# theremin.net
KiCad netlist of a schematic drawn in Altium Designer
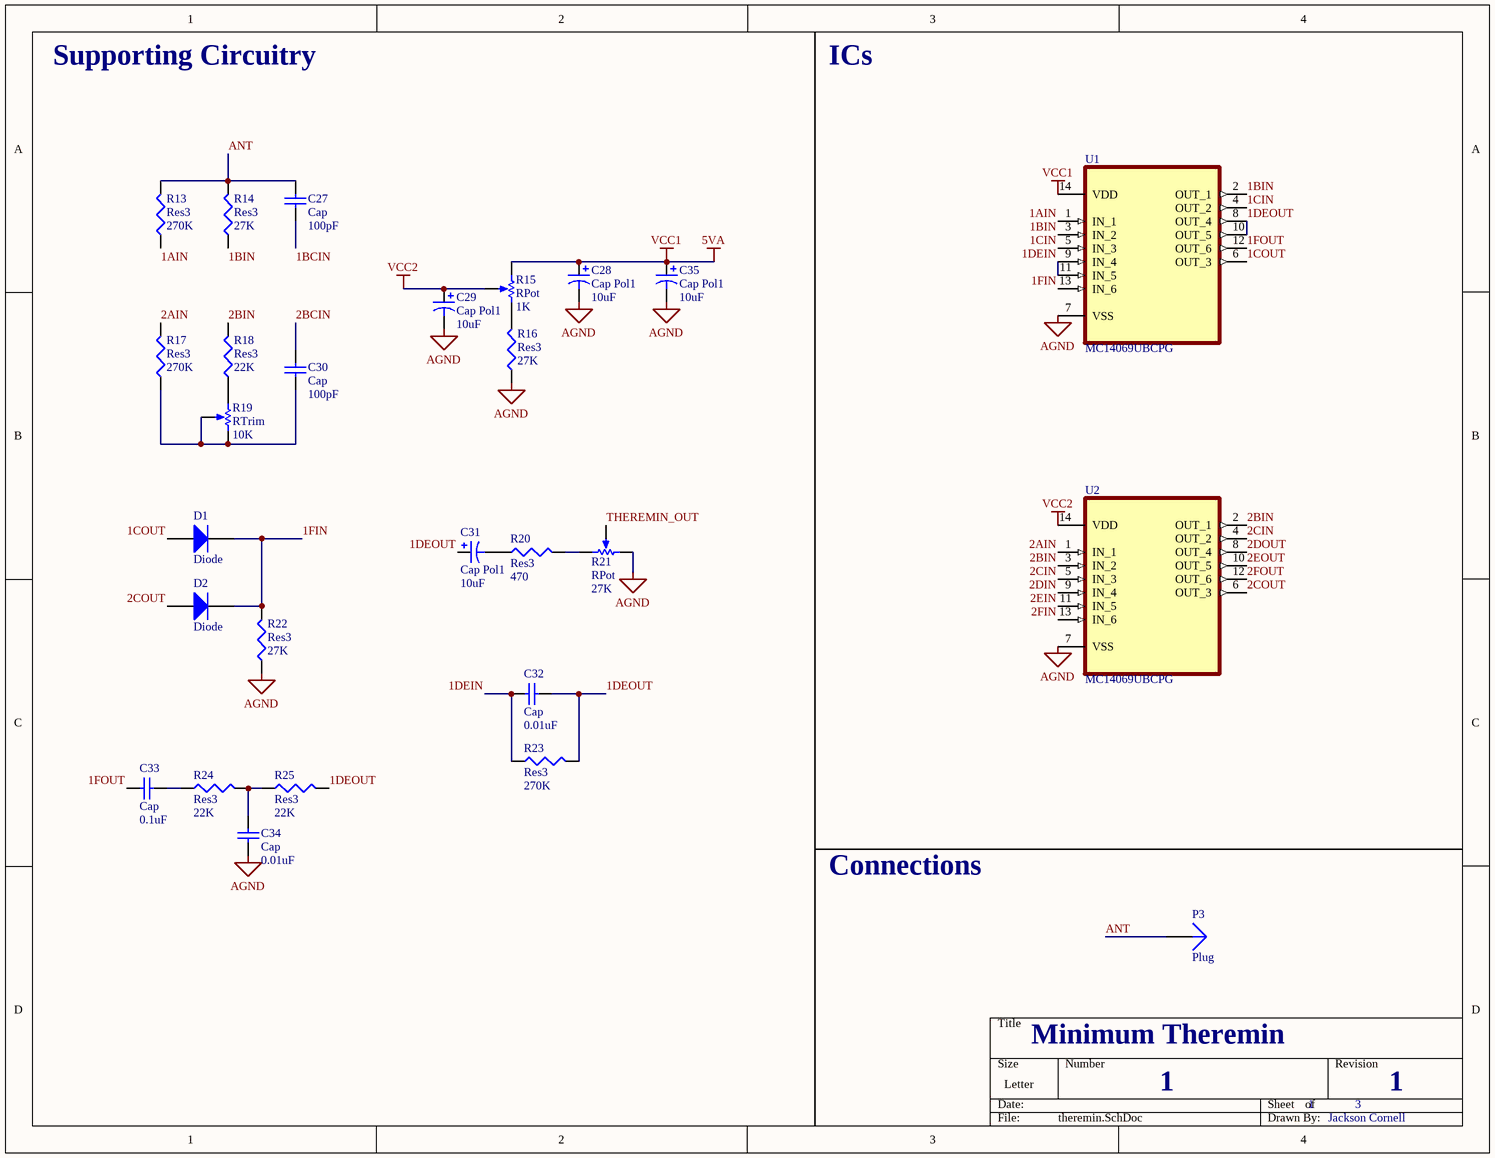
[diagram p0: theremin.SchDoc]

(export (version "E")
  (design (tool "Eeschema 10.0.6"))
  (components
    (comp (ref "C27")
      (value "Cap")
      (footprint "RAD-0.3")
      (description "Capacitor")
      (fields (field (name "ALTIUM_VALUE") "100pF") (field (name "PUBLISHER") "Altium Limited"))
      (libsource (lib "Miscellaneous Devices") (part "Cap"))
    )
    (comp (ref "C28")
      (value "Cap Pol1")
      (footprint "RB7.6-15")
      (description "Polarized Capacitor (Radial)")
      (fields (field (name "ALTIUM_VALUE") "10uF") (field (name "PUBLISHER") "Altium Limited"))
      (libsource (lib "Miscellaneous Devices") (part "Cap Pol1"))
    )
    (comp (ref "C29")
      (value "Cap Pol1")
      (footprint "RB7.6-15")
      (description "Polarized Capacitor (Radial)")
      (fields (field (name "ALTIUM_VALUE") "10uF") (field (name "PUBLISHER") "Altium Limited"))
      (libsource (lib "Miscellaneous Devices") (part "Cap Pol1"))
    )
    (comp (ref "C30")
      (value "Cap")
      (footprint "RAD-0.3")
      (description "Capacitor")
      (fields (field (name "ALTIUM_VALUE") "100pF") (field (name "PUBLISHER") "Altium Limited"))
      (libsource (lib "Miscellaneous Devices") (part "Cap"))
    )
    (comp (ref "C31")
      (value "Cap Pol1")
      (footprint "RB7.6-15")
      (description "Polarized Capacitor (Radial)")
      (fields (field (name "ALTIUM_VALUE") "10uF") (field (name "PUBLISHER") "Altium Limited"))
      (libsource (lib "Miscellaneous Devices") (part "Cap Pol1"))
    )
    (comp (ref "C32")
      (value "Cap")
      (footprint "RAD-0.3")
      (description "Capacitor")
      (fields (field (name "ALTIUM_VALUE") "0.01uF") (field (name "PUBLISHER") "Altium Limited"))
      (libsource (lib "Miscellaneous Devices") (part "Cap"))
    )
    (comp (ref "C33")
      (value "Cap")
      (footprint "RAD-0.3")
      (description "Capacitor")
      (fields (field (name "ALTIUM_VALUE") "0.1uF") (field (name "PUBLISHER") "Altium Limited"))
      (libsource (lib "Miscellaneous Devices") (part "Cap"))
    )
    (comp (ref "C34")
      (value "Cap")
      (footprint "RAD-0.3")
      (description "Capacitor")
      (fields (field (name "ALTIUM_VALUE") "0.01uF") (field (name "PUBLISHER") "Altium Limited"))
      (libsource (lib "Miscellaneous Devices") (part "Cap"))
    )
    (comp (ref "C35")
      (value "Cap Pol1")
      (footprint "RB7.6-15")
      (description "Polarized Capacitor (Radial)")
      (fields (field (name "ALTIUM_VALUE") "10uF") (field (name "PUBLISHER") "Altium Limited"))
      (libsource (lib "Miscellaneous Devices") (part "Cap Pol1"))
    )
    (comp (ref "D1")
      (value "Diode")
      (footprint "SMC")
      (description "Default Diode")
      (fields (field (name "PUBLISHER") "Altium Limited"))
      (libsource (lib "Miscellaneous Devices") (part "Diode"))
    )
    (comp (ref "D2")
      (value "Diode")
      (footprint "SMC")
      (description "Default Diode")
      (fields (field (name "PUBLISHER") "Altium Limited"))
      (libsource (lib "Miscellaneous Devices") (part "Diode"))
    )
    (comp (ref "P3")
      (value "Plug")
      (footprint "PIN1")
      (fields (field (name "PUBLISHER") "Altium Limited"))
      (libsource (lib "Miscellaneous Connectors") (part "Plug"))
    )
    (comp (ref "R13")
      (value "Res3")
      (footprint "J1-0603")
      (description "Resistor")
      (fields (field (name "ALTIUM_VALUE") "270K") (field (name "PUBLISHER") "Altium Limited"))
      (libsource (lib "Miscellaneous Devices") (part "Res3"))
    )
    (comp (ref "R14")
      (value "Res3")
      (footprint "J1-0603")
      (description "Resistor")
      (fields (field (name "ALTIUM_VALUE") "27K") (field (name "PUBLISHER") "Altium Limited"))
      (libsource (lib "Miscellaneous Devices") (part "Res3"))
    )
    (comp (ref "R15")
      (value "RPot")
      (footprint "VR5")
      (description "Potentiometer")
      (fields (field (name "ALTIUM_VALUE") "1K") (field (name "PUBLISHER") "Altium Limited"))
      (libsource (lib "Miscellaneous Devices") (part "RPot"))
    )
    (comp (ref "R16")
      (value "Res3")
      (footprint "J1-0603")
      (description "Resistor")
      (fields (field (name "ALTIUM_VALUE") "27K") (field (name "PUBLISHER") "Altium Limited"))
      (libsource (lib "Miscellaneous Devices") (part "Res3"))
    )
    (comp (ref "R17")
      (value "Res3")
      (footprint "J1-0603")
      (description "Resistor")
      (fields (field (name "ALTIUM_VALUE") "270K") (field (name "PUBLISHER") "Altium Limited"))
      (libsource (lib "Miscellaneous Devices") (part "Res3"))
    )
    (comp (ref "R18")
      (value "Res3")
      (footprint "J1-0603")
      (description "Resistor")
      (fields (field (name "ALTIUM_VALUE") "22K") (field (name "PUBLISHER") "Altium Limited"))
      (libsource (lib "Miscellaneous Devices") (part "Res3"))
    )
    (comp (ref "R19")
      (value "RTrim")
      (footprint "VR5")
      (description "Potentiometer")
      (fields (field (name "ALTIUM_VALUE") "10K") (field (name "PUBLISHER") "Altium Limited"))
      (libsource (lib "Miscellaneous Devices") (part "RPot"))
    )
    (comp (ref "R20")
      (value "Res3")
      (footprint "J1-0603")
      (description "Resistor")
      (fields (field (name "ALTIUM_VALUE") "470") (field (name "PUBLISHER") "Altium Limited"))
      (libsource (lib "Miscellaneous Devices") (part "Res3"))
    )
    (comp (ref "R21")
      (value "RPot")
      (footprint "VR5")
      (description "Potentiometer")
      (fields (field (name "ALTIUM_VALUE") "27K") (field (name "PUBLISHER") "Altium Limited"))
      (libsource (lib "Miscellaneous Devices") (part "RPot"))
    )
    (comp (ref "R22")
      (value "Res3")
      (footprint "J1-0603")
      (description "Resistor")
      (fields (field (name "ALTIUM_VALUE") "27K") (field (name "PUBLISHER") "Altium Limited"))
      (libsource (lib "Miscellaneous Devices") (part "Res3"))
    )
    (comp (ref "R23")
      (value "Res3")
      (footprint "J1-0603")
      (description "Resistor")
      (fields (field (name "ALTIUM_VALUE") "270K") (field (name "PUBLISHER") "Altium Limited"))
      (libsource (lib "Miscellaneous Devices") (part "Res3"))
    )
    (comp (ref "R24")
      (value "Res3")
      (footprint "J1-0603")
      (description "Resistor")
      (fields (field (name "ALTIUM_VALUE") "22K") (field (name "PUBLISHER") "Altium Limited"))
      (libsource (lib "Miscellaneous Devices") (part "Res3"))
    )
    (comp (ref "R25")
      (value "Res3")
      (footprint "J1-0603")
      (description "Resistor")
      (fields (field (name "ALTIUM_VALUE") "22K") (field (name "PUBLISHER") "Altium Limited"))
      (libsource (lib "Miscellaneous Devices") (part "Res3"))
    )
    (comp (ref "U1")
      (value "MC14069UBCPG")
      (footprint "DIP254P762X469-14")
      (description "Inverter IC 6 Channel - 14-PDIP")
      (fields (field (name "MF") "ON Semiconductor"))
      (libsource (lib "MC14069UBCPG") (part "MC14069UBCPG"))
    )
    (comp (ref "U2")
      (value "MC14069UBCPG")
      (footprint "DIP254P762X469-14")
      (description "Inverter IC 6 Channel - 14-PDIP")
      (fields (field (name "MF") "ON Semiconductor"))
      (libsource (lib "MC14069UBCPG") (part "MC14069UBCPG"))
    )
  )
  (nets
    (net (code "1") (name "/1AIN") (class "Default")
      (node (ref "R13") (pin "1") (pinfunction "1_1") (pintype "passive"))
      (node (ref "U1") (pin "1") (pinfunction "IN_1_1") (pintype "input"))
    )
    (net (code "2") (name "/1BCIN") (class "Default")
      (node (ref "C27") (pin "1") (pinfunction "1_1") (pintype "passive"))
    )
    (net (code "3") (name "/1BIN") (class "Default")
      (node (ref "R14") (pin "1") (pinfunction "1_1") (pintype "passive"))
      (node (ref "U1") (pin "2") (pinfunction "OUT_1_2") (pintype "output"))
      (node (ref "U1") (pin "3") (pinfunction "IN_2_3") (pintype "input"))
    )
    (net (code "4") (name "/1CIN") (class "Default")
      (node (ref "U1") (pin "4") (pinfunction "OUT_2_4") (pintype "output"))
      (node (ref "U1") (pin "5") (pinfunction "IN_3_5") (pintype "input"))
    )
    (net (code "5") (name "/1COUT") (class "Default")
      (node (ref "D1") (pin "1") (pinfunction "A_1") (pintype "passive"))
      (node (ref "U1") (pin "6") (pinfunction "OUT_3_6") (pintype "output"))
    )
    (net (code "6") (name "/1DEIN") (class "Default")
      (node (ref "C32") (pin "1") (pinfunction "1_1") (pintype "passive"))
      (node (ref "R23") (pin "1") (pinfunction "1_1") (pintype "passive"))
      (node (ref "U1") (pin "11") (pinfunction "IN_5_11") (pintype "input"))
      (node (ref "U1") (pin "9") (pinfunction "IN_4_9") (pintype "input"))
    )
    (net (code "7") (name "/1DEOUT") (class "Default")
      (node (ref "C31") (pin "1") (pinfunction "1_1") (pintype "passive"))
      (node (ref "C32") (pin "2") (pinfunction "2_2") (pintype "passive"))
      (node (ref "R23") (pin "2") (pinfunction "2_2") (pintype "passive"))
      (node (ref "R25") (pin "2") (pinfunction "2_2") (pintype "passive"))
      (node (ref "U1") (pin "10") (pinfunction "OUT_5_10") (pintype "output"))
      (node (ref "U1") (pin "8") (pinfunction "OUT_4_8") (pintype "output"))
    )
    (net (code "8") (name "/1FIN") (class "Default")
      (node (ref "D1") (pin "2") (pinfunction "K_2") (pintype "passive"))
      (node (ref "D2") (pin "2") (pinfunction "K_2") (pintype "passive"))
      (node (ref "R22") (pin "2") (pinfunction "2_2") (pintype "passive"))
      (node (ref "U1") (pin "13") (pinfunction "IN_6_13") (pintype "input"))
    )
    (net (code "9") (name "/1FOUT") (class "Default")
      (node (ref "C33") (pin "1") (pinfunction "1_1") (pintype "passive"))
      (node (ref "U1") (pin "12") (pinfunction "OUT_6_12") (pintype "output"))
    )
    (net (code "10") (name "/2AIN") (class "Default")
      (node (ref "R17") (pin "2") (pinfunction "2_2") (pintype "passive"))
      (node (ref "U2") (pin "1") (pinfunction "IN_1_1") (pintype "input"))
    )
    (net (code "11") (name "/2BCIN") (class "Default")
      (node (ref "C30") (pin "2") (pinfunction "2_2") (pintype "passive"))
    )
    (net (code "12") (name "/2BIN") (class "Default")
      (node (ref "R18") (pin "2") (pinfunction "2_2") (pintype "passive"))
      (node (ref "U2") (pin "2") (pinfunction "OUT_1_2") (pintype "output"))
      (node (ref "U2") (pin "3") (pinfunction "IN_2_3") (pintype "input"))
    )
    (net (code "13") (name "/2CIN") (class "Default")
      (node (ref "U2") (pin "4") (pinfunction "OUT_2_4") (pintype "output"))
      (node (ref "U2") (pin "5") (pinfunction "IN_3_5") (pintype "input"))
    )
    (net (code "14") (name "/2COUT") (class "Default")
      (node (ref "D2") (pin "1") (pinfunction "A_1") (pintype "passive"))
      (node (ref "U2") (pin "6") (pinfunction "OUT_3_6") (pintype "output"))
    )
    (net (code "15") (name "/2DIN") (class "Default")
      (node (ref "U2") (pin "9") (pinfunction "IN_4_9") (pintype "input"))
    )
    (net (code "16") (name "/2DOUT") (class "Default")
      (node (ref "U2") (pin "8") (pinfunction "OUT_4_8") (pintype "output"))
    )
    (net (code "17") (name "/2EIN") (class "Default")
      (node (ref "U2") (pin "11") (pinfunction "IN_5_11") (pintype "input"))
    )
    (net (code "18") (name "/2EOUT") (class "Default")
      (node (ref "U2") (pin "10") (pinfunction "OUT_5_10") (pintype "output"))
    )
    (net (code "19") (name "/2FIN") (class "Default")
      (node (ref "U2") (pin "13") (pinfunction "IN_6_13") (pintype "input"))
    )
    (net (code "20") (name "/2FOUT") (class "Default")
      (node (ref "U2") (pin "12") (pinfunction "OUT_6_12") (pintype "output"))
    )
    (net (code "21") (name "/ANT") (class "Default")
      (node (ref "C27") (pin "2") (pinfunction "2_2") (pintype "passive"))
      (node (ref "P3") (pin "1") (pinfunction "1_1") (pintype "passive"))
      (node (ref "R13") (pin "2") (pinfunction "2_2") (pintype "passive"))
      (node (ref "R14") (pin "2") (pinfunction "2_2") (pintype "passive"))
    )
    (net (code "22") (name "/THEREMIN_OUT") (class "Default")
      (node (ref "R21") (pin "3") (pinfunction "TAP_3") (pintype "passive"))
    )
    (net (code "23") (name "5VA") (class "Default")
      (node (ref "C28") (pin "1") (pinfunction "1_1") (pintype "passive"))
      (node (ref "C35") (pin "1") (pinfunction "1_1") (pintype "passive"))
      (node (ref "R15") (pin "1") (pinfunction "TOP_1") (pintype "passive"))
      (node (ref "U1") (pin "14") (pinfunction "VDD_14") (pintype "power_in"))
    )
    (net (code "24") (name "AGND") (class "Default")
      (node (ref "C28") (pin "2") (pinfunction "2_2") (pintype "passive"))
      (node (ref "C29") (pin "2") (pinfunction "2_2") (pintype "passive"))
      (node (ref "C34") (pin "1") (pinfunction "1_1") (pintype "passive"))
      (node (ref "C35") (pin "2") (pinfunction "2_2") (pintype "passive"))
      (node (ref "R16") (pin "1") (pinfunction "1_1") (pintype "passive"))
      (node (ref "R21") (pin "1") (pinfunction "TOP_1") (pintype "passive"))
      (node (ref "R22") (pin "1") (pinfunction "1_1") (pintype "passive"))
      (node (ref "U1") (pin "7") (pinfunction "VSS_7") (pintype "power_in"))
      (node (ref "U2") (pin "7") (pinfunction "VSS_7") (pintype "power_in"))
    )
    (net (code "25") (name "Net-(C31-Pad2)") (class "Default")
      (node (ref "C31") (pin "2") (pinfunction "2_2") (pintype "passive"))
      (node (ref "R20") (pin "1") (pinfunction "1_1") (pintype "passive"))
    )
    (net (code "26") (name "Net-(C33-Pad2)") (class "Default")
      (node (ref "C33") (pin "2") (pinfunction "2_2") (pintype "passive"))
      (node (ref "R24") (pin "1") (pinfunction "1_1") (pintype "passive"))
    )
    (net (code "27") (name "Net-(C34-Pad2)") (class "Default")
      (node (ref "C34") (pin "2") (pinfunction "2_2") (pintype "passive"))
      (node (ref "R24") (pin "2") (pinfunction "2_2") (pintype "passive"))
      (node (ref "R25") (pin "1") (pinfunction "1_1") (pintype "passive"))
    )
    (net (code "28") (name "Net-(R15-BOT)") (class "Default")
      (node (ref "R15") (pin "2") (pinfunction "BOT_2") (pintype "passive"))
      (node (ref "R16") (pin "2") (pinfunction "2_2") (pintype "passive"))
    )
    (net (code "29") (name "Net-(R19-BOT)") (class "Default")
      (node (ref "C30") (pin "1") (pinfunction "1_1") (pintype "passive"))
      (node (ref "R17") (pin "1") (pinfunction "1_1") (pintype "passive"))
      (node (ref "R19") (pin "2") (pinfunction "BOT_2") (pintype "passive"))
      (node (ref "R19") (pin "3") (pinfunction "TAP_3") (pintype "passive"))
    )
    (net (code "30") (name "Net-(R19-TOP)") (class "Default")
      (node (ref "R18") (pin "1") (pinfunction "1_1") (pintype "passive"))
      (node (ref "R19") (pin "1") (pinfunction "TOP_1") (pintype "passive"))
    )
    (net (code "31") (name "Net-(R21-BOT)") (class "Default")
      (node (ref "R20") (pin "2") (pinfunction "2_2") (pintype "passive"))
      (node (ref "R21") (pin "2") (pinfunction "BOT_2") (pintype "passive"))
    )
    (net (code "32") (name "VCC2") (class "Default")
      (node (ref "C29") (pin "1") (pinfunction "1_1") (pintype "passive"))
      (node (ref "R15") (pin "3") (pinfunction "TAP_3") (pintype "passive"))
      (node (ref "U2") (pin "14") (pinfunction "VDD_14") (pintype "power_in"))
    )
  )
)
